# SparkFun_Opto_Isolator_Breakout.net
KiCad netlist of a schematic drawn in EAGLE
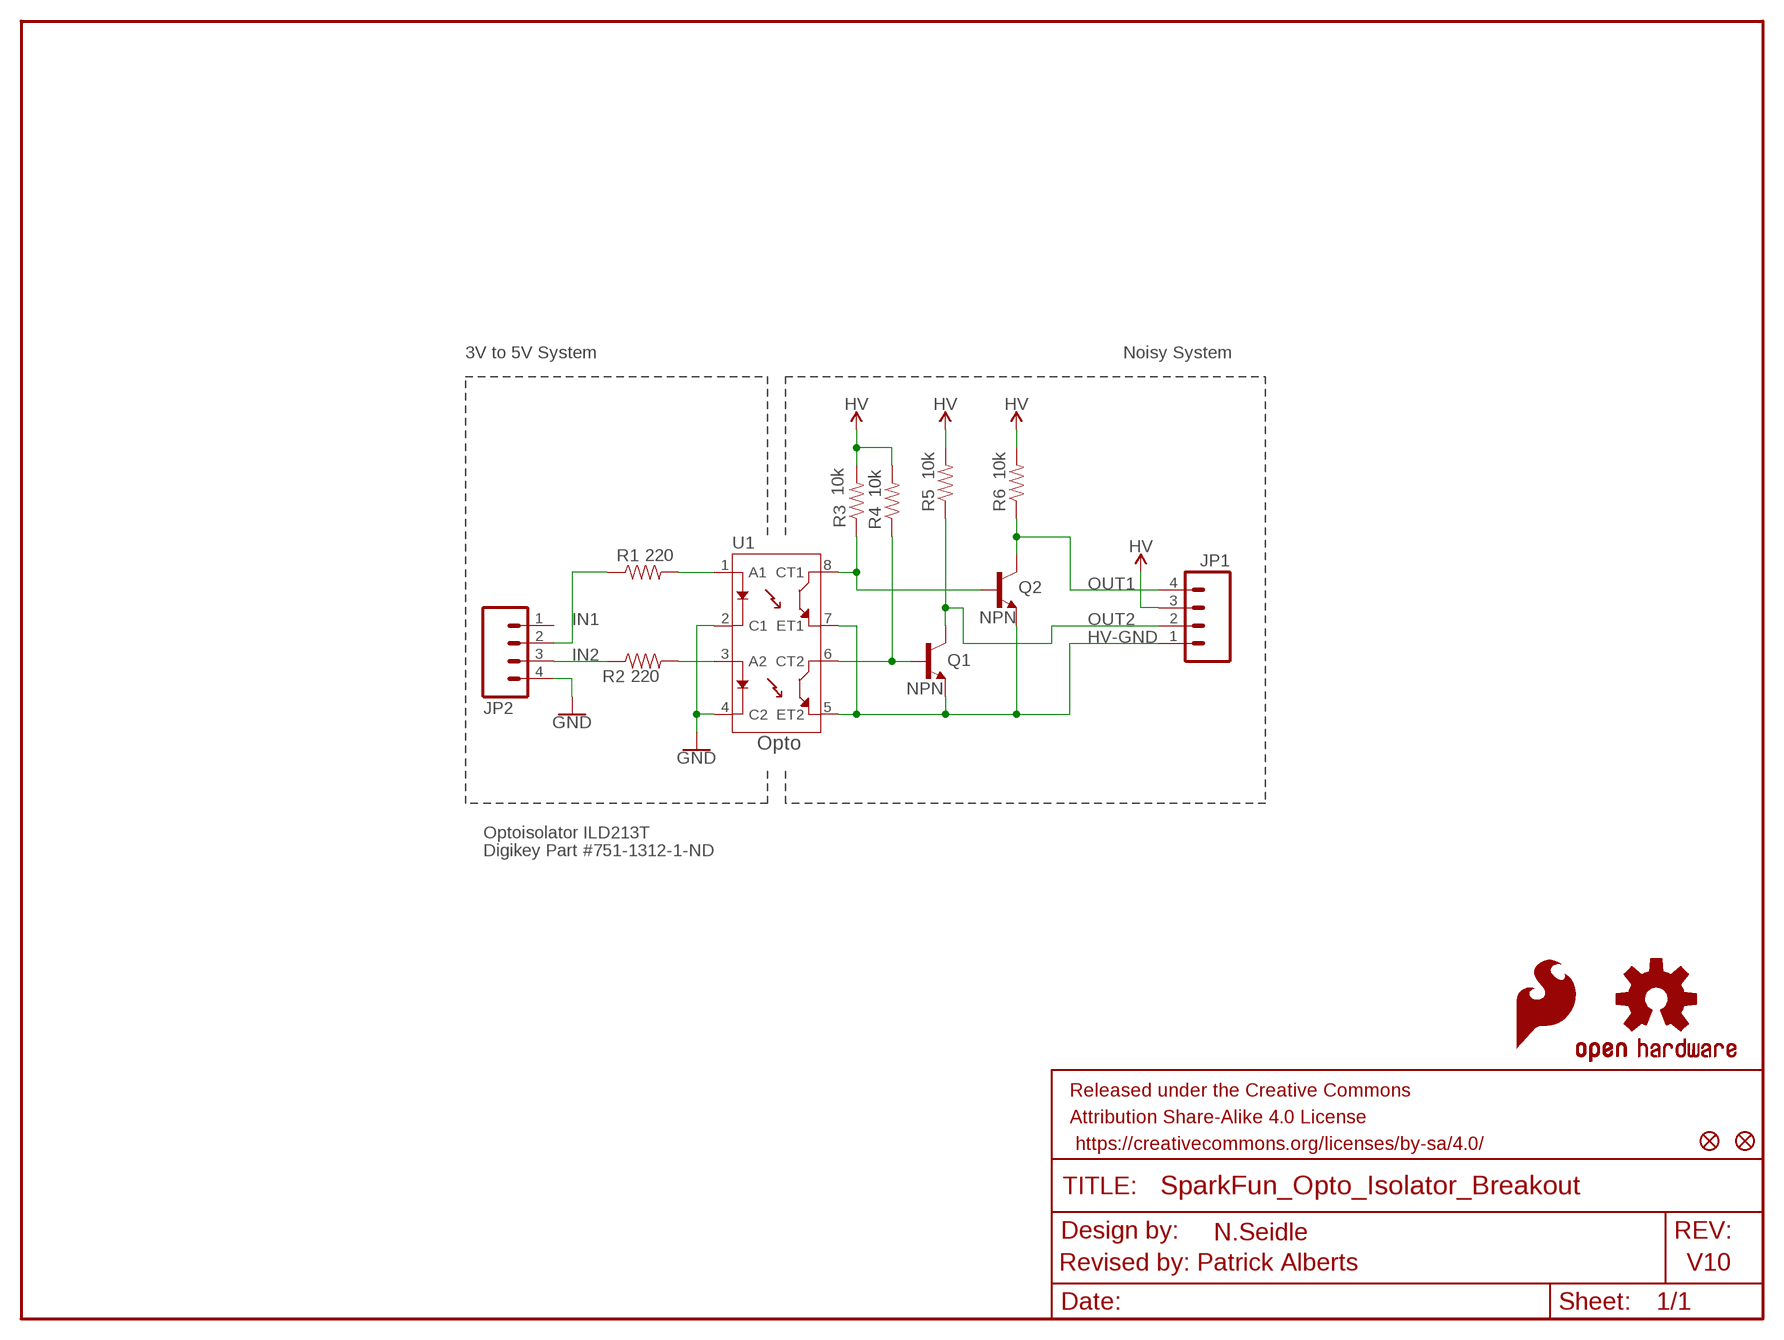
[diagram p0: schematic, sheet 1]

(export (version "E")
  (design (tool "Eeschema 10.0.6"))
  (components
    (comp (ref "FRAME1")
      (value "FRAME-LETTER")
      (footprint "eagle-import:CREATIVE_COMMONS")
      (fields (field (name "DESIGNER") "NAME"))
      (libsource (lib "eagle-import") (part "FRAME-LETTER"))
    )
    (comp (ref "JP1")
      (value "M04PTH")
      (footprint "eagle-import:1X04")
      (libsource (lib "eagle-import") (part "M04PTH"))
    )
    (comp (ref "JP2")
      (value "M04PTH")
      (footprint "eagle-import:1X04")
      (libsource (lib "eagle-import") (part "M04PTH"))
    )
    (comp (ref "LOGO1")
      (value "OSHW-LOGOS")
      (footprint "eagle-import:OSHW-LOGO-S")
      (libsource (lib "eagle-import") (part "OSHW-LOGOS"))
    )
    (comp (ref "LOGO2")
      (value "SFE_LOGO_FLAME.1_INCH")
      (footprint "eagle-import:SFE_LOGO_FLAME_.1")
      (libsource (lib "eagle-import") (part "SFE_LOGO_FLAME.1_INCH"))
    )
    (comp (ref "Q1")
      (value "NPN")
      (footprint "eagle-import:SOT23-3")
      (libsource (lib "eagle-import") (part "TRANSISTOR_NPNMMBT2222A"))
    )
    (comp (ref "Q2")
      (value "NPN")
      (footprint "eagle-import:SOT23-3")
      (libsource (lib "eagle-import") (part "TRANSISTOR_NPNMMBT2222A"))
    )
    (comp (ref "R1")
      (value "220")
      (footprint "eagle-import:0603")
      (libsource (lib "eagle-import") (part "220OHM-0603-1/10W-1%"))
    )
    (comp (ref "R2")
      (value "220")
      (footprint "eagle-import:0603")
      (libsource (lib "eagle-import") (part "220OHM-0603-1/10W-1%"))
    )
    (comp (ref "R3")
      (value "10k")
      (footprint "eagle-import:0603")
      (libsource (lib "eagle-import") (part "10KOHM-0603-1/10W-1%"))
    )
    (comp (ref "R4")
      (value "10k")
      (footprint "eagle-import:0603")
      (libsource (lib "eagle-import") (part "10KOHM-0603-1/10W-1%"))
    )
    (comp (ref "R5")
      (value "10k")
      (footprint "eagle-import:0603")
      (libsource (lib "eagle-import") (part "10KOHM-0603-1/10W-1%"))
    )
    (comp (ref "R6")
      (value "10k")
      (footprint "eagle-import:0603")
      (libsource (lib "eagle-import") (part "10KOHM-0603-1/10W-1%"))
    )
    (comp (ref "U$2")
      (value "FIDUCIALUFIDUCIAL")
      (footprint "eagle-import:MICRO-FIDUCIAL")
      (libsource (lib "eagle-import") (part "FIDUCIALUFIDUCIAL"))
    )
    (comp (ref "U$3")
      (value "FIDUCIALUFIDUCIAL")
      (footprint "eagle-import:MICRO-FIDUCIAL")
      (libsource (lib "eagle-import") (part "FIDUCIALUFIDUCIAL"))
    )
    (comp (ref "U1")
      (value "ILD213T-IDL213T")
      (footprint "eagle-import:SO08")
      (libsource (lib "eagle-import") (part "ILD213T-IDL213T"))
    )
  )
  (nets
    (net (code "1") (name "/HV-GND") (class "Default")
      (node (ref "JP1") (pin "1") (pinfunction "1_1") (pintype "passive"))
      (node (ref "Q1") (pin "2") (pinfunction "E_2") (pintype "passive"))
      (node (ref "Q2") (pin "2") (pinfunction "E_2") (pintype "passive"))
      (node (ref "U1") (pin "5") (pinfunction "ET2_5") (pintype "bidirectional"))
      (node (ref "U1") (pin "7") (pinfunction "ET1_7") (pintype "bidirectional"))
    )
    (net (code "2") (name "/IN1") (class "Default")
      (node (ref "JP2") (pin "2") (pinfunction "2_2") (pintype "passive"))
      (node (ref "R1") (pin "1") (pinfunction "1_1") (pintype "passive"))
    )
    (net (code "3") (name "/IN2") (class "Default")
      (node (ref "JP2") (pin "3") (pinfunction "3_3") (pintype "passive"))
      (node (ref "R2") (pin "1") (pinfunction "1_1") (pintype "passive"))
    )
    (net (code "4") (name "/OUT1") (class "Default")
      (node (ref "JP1") (pin "4") (pinfunction "4_4") (pintype "passive"))
      (node (ref "Q2") (pin "3") (pinfunction "C_3") (pintype "passive"))
      (node (ref "R6") (pin "1") (pinfunction "1_1") (pintype "passive"))
    )
    (net (code "5") (name "/OUT2") (class "Default")
      (node (ref "JP1") (pin "2") (pinfunction "2_2") (pintype "passive"))
      (node (ref "Q1") (pin "3") (pinfunction "C_3") (pintype "passive"))
      (node (ref "R5") (pin "1") (pinfunction "1_1") (pintype "passive"))
    )
    (net (code "6") (name "GND") (class "Default")
      (node (ref "JP2") (pin "4") (pinfunction "4_4") (pintype "passive"))
      (node (ref "U1") (pin "2") (pinfunction "C1_2") (pintype "bidirectional"))
      (node (ref "U1") (pin "4") (pinfunction "C2_4") (pintype "bidirectional"))
    )
    (net (code "7") (name "HV") (class "Default")
      (node (ref "JP1") (pin "3") (pinfunction "3_3") (pintype "passive"))
      (node (ref "R3") (pin "2") (pinfunction "2_2") (pintype "passive"))
      (node (ref "R4") (pin "2") (pinfunction "2_2") (pintype "passive"))
      (node (ref "R5") (pin "2") (pinfunction "2_2") (pintype "passive"))
      (node (ref "R6") (pin "2") (pinfunction "2_2") (pintype "passive"))
    )
    (net (code "8") (name "Net-(Q1-B)") (class "Default")
      (node (ref "Q1") (pin "1") (pinfunction "B_1") (pintype "passive"))
      (node (ref "R4") (pin "1") (pinfunction "1_1") (pintype "passive"))
      (node (ref "U1") (pin "6") (pinfunction "CT2_6") (pintype "bidirectional"))
    )
    (net (code "9") (name "Net-(Q2-B)") (class "Default")
      (node (ref "Q2") (pin "1") (pinfunction "B_1") (pintype "passive"))
      (node (ref "R3") (pin "1") (pinfunction "1_1") (pintype "passive"))
      (node (ref "U1") (pin "8") (pinfunction "CT1_8") (pintype "bidirectional"))
    )
    (net (code "10") (name "Net-(U1-A1)") (class "Default")
      (node (ref "R1") (pin "2") (pinfunction "2_2") (pintype "passive"))
      (node (ref "U1") (pin "1") (pinfunction "A1_1") (pintype "bidirectional"))
    )
    (net (code "11") (name "Net-(U1-A2)") (class "Default")
      (node (ref "R2") (pin "2") (pinfunction "2_2") (pintype "passive"))
      (node (ref "U1") (pin "3") (pinfunction "A2_3") (pintype "bidirectional"))
    )
    (net (code "12") (name "unconnected-(JP2-Pad1)") (class "Default")
      (node (ref "JP2") (pin "1") (pinfunction "1_1") (pintype "passive"))
    )
  )
)
